# ServoConnector.net
KiCad netlist of a schematic drawn in Altium Designer
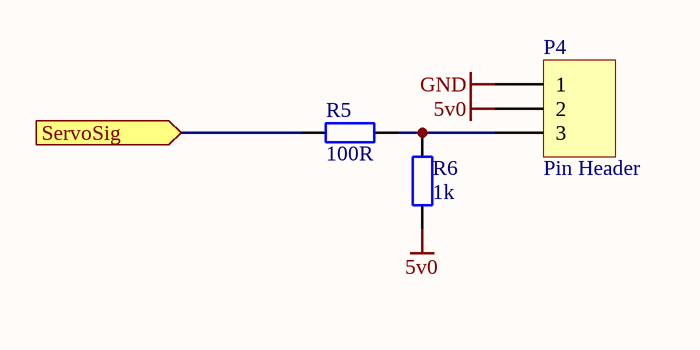
[diagram p0: ServoConnector.SchDoc]

(export (version "E")
  (design (tool "Eeschema 10.0.6"))
  (components
    (comp (ref "P4")
      (value "Pin Header")
      (footprint "PH1x3_2.54")
      (description "Con1x3")
      (fields (field (name "PART NUMBER") "PH1x3") (field (name "AUTHOR") "Willy Pietersz"))
      (libsource (lib "OurDb") (part "Con1x3"))
    )
    (comp (ref "R5")
      (value "100R")
      (footprint "R0805")
      (description "Resistor")
      (fields
        (field (name "POWER") "0.25W")
        (field (name "TOLERANCE") "0.05")
        (field (name "PUBLISHER") "Altium Limited")
        (field (name "AUTHOR") "Willy Pietersz")
      )
      (libsource (lib "") (part "RESISTOR_1"))
    )
    (comp (ref "R6")
      (value "1k")
      (footprint "R0805")
      (description "Resistor")
      (fields
        (field (name "PART NUMBER") "1K")
        (field (name "POWER") "0.25W")
        (field (name "PUBLISHER") "Altium Limited")
        (field (name "AUTHOR") "Willy Pietersz")
      )
      (libsource (lib "OurDb") (part "RESISTOR"))
    )
  )
  (nets
    (net (code "1") (name "/ServoSig") (class "Default")
      (node (ref "R5") (pin "2") (pinfunction "2_2") (pintype "passive"))
    )
    (net (code "2") (name "5v0") (class "Default")
      (node (ref "P4") (pin "2") (pinfunction "2_2") (pintype "passive"))
      (node (ref "R6") (pin "2") (pinfunction "2_2") (pintype "passive"))
    )
    (net (code "3") (name "GND") (class "Default")
      (node (ref "P4") (pin "1") (pinfunction "1_1") (pintype "passive"))
    )
    (net (code "4") (name "Net-(P4-Pad3)") (class "Default")
      (node (ref "P4") (pin "3") (pinfunction "3_3") (pintype "passive"))
      (node (ref "R5") (pin "1") (pinfunction "1_1") (pintype "passive"))
      (node (ref "R6") (pin "1") (pinfunction "1_1") (pintype "passive"))
    )
  )
)
